# CPLD_Programming.net
KiCad netlist of a schematic drawn in Altium Designer
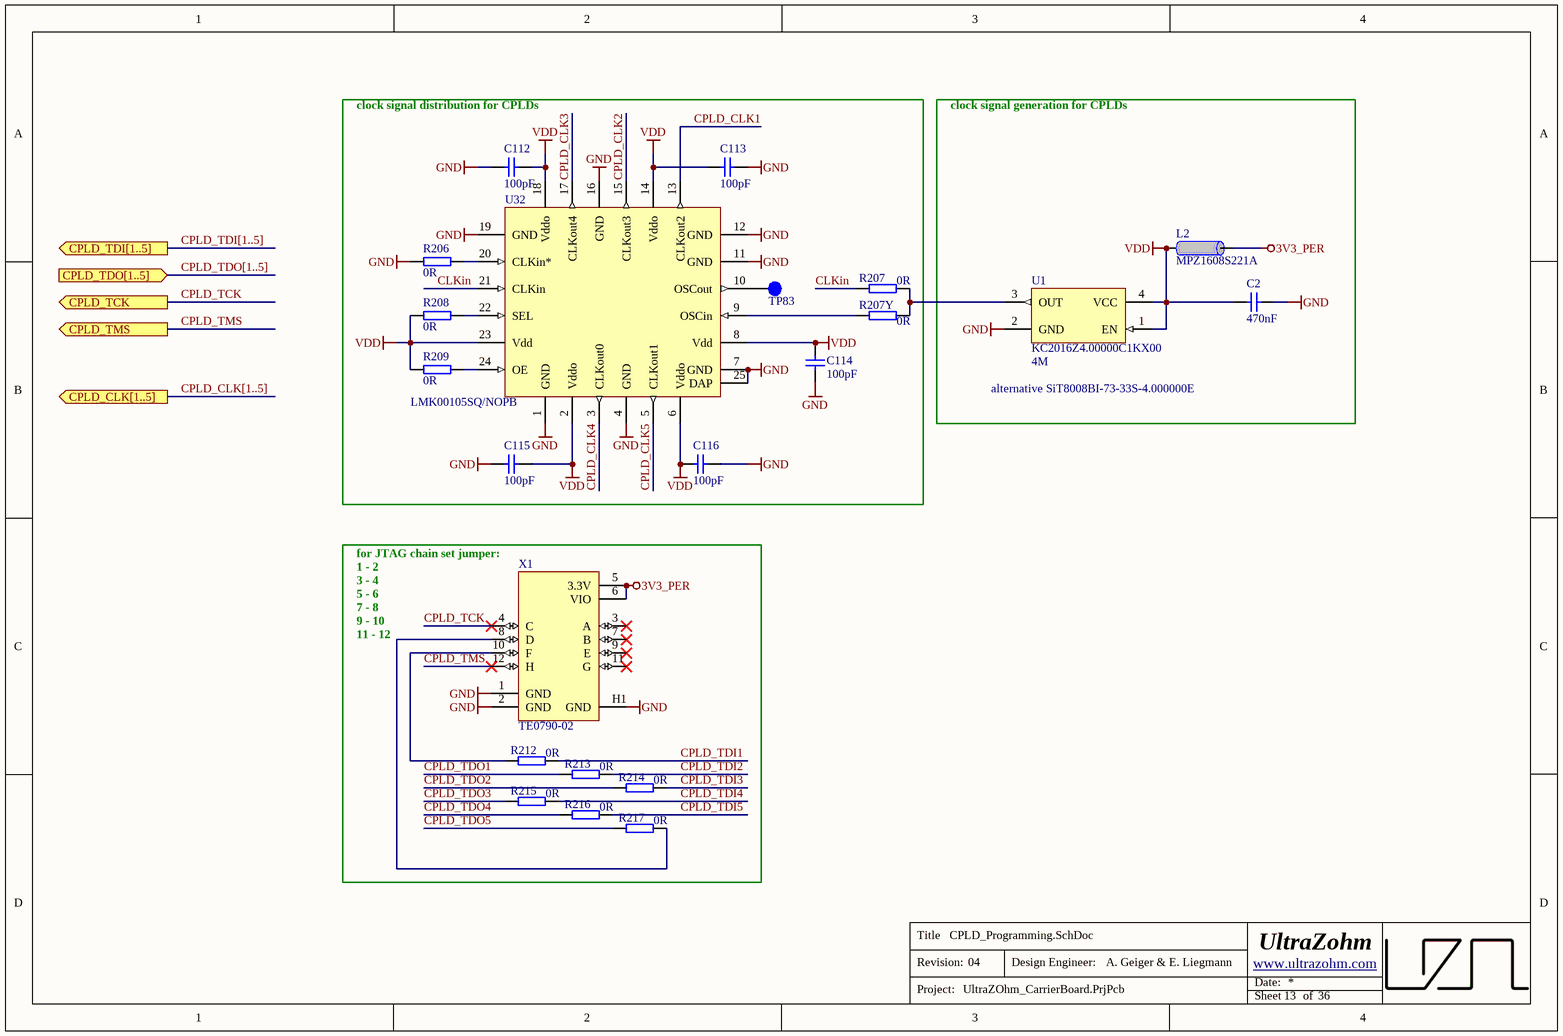
[diagram p0: CPLD_Programming.SchDoc]

(export (version "E")
  (design (tool "Eeschema 10.0.6"))
  (components
    (comp (ref "C2")
      (value "470nF")
      (footprint "CAPC1608X90N_V")
      (description "KON 470nF 50V X7R SMD  BF 1608 (0603)")
      (fields (field (name "VOLTAGE") "50V"))
      (libsource (lib "TE") (part "CAP-NP"))
    )
    (comp (ref "C112")
      (value "100pF")
      (footprint "CAPC1608X90N_V")
      (description "KON 100pF 50V NP0 ±5% SMD BF 1608 (0603)")
      (fields (field (name "TOLERANCE") "±5%") (field (name "VOLTAGE") "50V"))
      (libsource (lib "TE") (part "CAP-NP"))
    )
    (comp (ref "C113")
      (value "100pF")
      (footprint "CAPC1608X90N_V")
      (description "KON 100pF 50V NP0 ±5% SMD BF 1608 (0603)")
      (fields (field (name "TOLERANCE") "±5%") (field (name "VOLTAGE") "50V"))
      (libsource (lib "TE") (part "CAP-NP"))
    )
    (comp (ref "C114")
      (value "100pF")
      (footprint "CAPC1608X90N_V")
      (description "KON 100pF 50V NP0 ±5% SMD BF 1608 (0603)")
      (fields (field (name "TOLERANCE") "±5%") (field (name "VOLTAGE") "50V"))
      (libsource (lib "TE") (part "CAP-NP"))
    )
    (comp (ref "C115")
      (value "100pF")
      (footprint "CAPC1608X90N_V")
      (description "KON 100pF 50V NP0 ±5% SMD BF 1608 (0603)")
      (fields (field (name "TOLERANCE") "±5%") (field (name "VOLTAGE") "50V"))
      (libsource (lib "TE") (part "CAP-NP"))
    )
    (comp (ref "C116")
      (value "100pF")
      (footprint "CAPC1608X90N_V")
      (description "KON 100pF 50V NP0 ±5% SMD BF 1608 (0603)")
      (fields (field (name "TOLERANCE") "±5%") (field (name "VOLTAGE") "50V"))
      (libsource (lib "TE") (part "CAP-NP"))
    )
    (comp (ref "L2")
      (value "MPZ1608S221A")
      (footprint "INDC1608X95N_V")
      (description "Ferritdurchführung MPZ1608S221A")
      (libsource (lib "TE") (part "Ferritperle"))
    )
    (comp (ref "R206")
      (value "0R")
      (footprint "R_0603_TE")
      (description "Generic resistor")
      (fields
        (field (name "TOLERANCE") "1 %")
        (field (name "MANUFACTURER PART NUMBER") "UZgen_R_0603_0R")
        (field (name "CREATED FROM") "UZgenTool")
      )
      (libsource (lib "user") (part "RES"))
    )
    (comp (ref "R207")
      (value "0R")
      (footprint "R_0603_TE")
      (description "Generic resistor")
      (fields
        (field (name "TOLERANCE") "1 %")
        (field (name "MANUFACTURER PART NUMBER") "UZgen_R_0603_0R")
        (field (name "CREATED FROM") "UZgenTool")
      )
      (libsource (lib "user") (part "RES"))
    )
    (comp (ref "R207Y")
      (value "0R")
      (footprint "R_0603_TE")
      (description "Generic resistor")
      (fields
        (field (name "TOLERANCE") "1 %")
        (field (name "MANUFACTURER PART NUMBER") "UZgen_R_0603_0R")
        (field (name "CREATED FROM") "UZgenTool")
      )
      (libsource (lib "user") (part "RES"))
    )
    (comp (ref "R208")
      (value "0R")
      (footprint "R_0603_TE")
      (description "Generic resistor")
      (fields
        (field (name "TOLERANCE") "1 %")
        (field (name "MANUFACTURER PART NUMBER") "UZgen_R_0603_0R")
        (field (name "CREATED FROM") "UZgenTool")
      )
      (libsource (lib "user") (part "RES"))
    )
    (comp (ref "R209")
      (value "0R")
      (footprint "R_0603_TE")
      (description "Generic resistor")
      (fields
        (field (name "TOLERANCE") "1 %")
        (field (name "MANUFACTURER PART NUMBER") "UZgen_R_0603_0R")
        (field (name "CREATED FROM") "UZgenTool")
      )
      (libsource (lib "user") (part "RES"))
    )
    (comp (ref "R212")
      (value "0R")
      (footprint "R_0603_TE")
      (description "Generic resistor")
      (fields
        (field (name "TOLERANCE") "1 %")
        (field (name "MANUFACTURER PART NUMBER") "UZgen_R_0603_0R")
        (field (name "CREATED FROM") "UZgenTool")
      )
      (libsource (lib "user") (part "RES"))
    )
    (comp (ref "R213")
      (value "0R")
      (footprint "R_0603_TE")
      (description "Generic resistor")
      (fields
        (field (name "TOLERANCE") "1 %")
        (field (name "MANUFACTURER PART NUMBER") "UZgen_R_0603_0R")
        (field (name "CREATED FROM") "UZgenTool")
      )
      (libsource (lib "user") (part "RES"))
    )
    (comp (ref "R214")
      (value "0R")
      (footprint "R_0603_TE")
      (description "Generic resistor")
      (fields
        (field (name "TOLERANCE") "1 %")
        (field (name "MANUFACTURER PART NUMBER") "UZgen_R_0603_0R")
        (field (name "CREATED FROM") "UZgenTool")
      )
      (libsource (lib "user") (part "RES"))
    )
    (comp (ref "R215")
      (value "0R")
      (footprint "R_0603_TE")
      (description "Generic resistor")
      (fields
        (field (name "TOLERANCE") "1 %")
        (field (name "MANUFACTURER PART NUMBER") "UZgen_R_0603_0R")
        (field (name "CREATED FROM") "UZgenTool")
      )
      (libsource (lib "user") (part "RES"))
    )
    (comp (ref "R216")
      (value "0R")
      (footprint "R_0603_TE")
      (description "Generic resistor")
      (fields
        (field (name "TOLERANCE") "1 %")
        (field (name "MANUFACTURER PART NUMBER") "UZgen_R_0603_0R")
        (field (name "CREATED FROM") "UZgenTool")
      )
      (libsource (lib "user") (part "RES"))
    )
    (comp (ref "R217")
      (value "0R")
      (footprint "R_0603_TE")
      (description "Generic resistor")
      (fields
        (field (name "TOLERANCE") "1 %")
        (field (name "MANUFACTURER PART NUMBER") "UZgen_R_0603_0R")
        (field (name "CREATED FROM") "UZgenTool")
      )
      (libsource (lib "user") (part "RES"))
    )
    (comp (ref "TP83") (value "Testpoint 1mm") (footprint "TP_1mm") (libsource (lib "TE") (part "TP")))
    (comp (ref "U1")
      (value "KC2016Z4.00000C1KX00")
      (footprint "2016")
      (description "KC2016Z4.00000C1KX00 Oszillator 4.000000MHz")
      (fields
        (field (name "ALTIUM_VALUE") "4M")
        (field (name "VOLTAGE") "1.8-3.3V")
        (field (name "TOLERANCE") "20ppm")
      )
      (libsource (lib "TE") (part "KC3225K"))
    )
    (comp (ref "U32")
      (value "LMK00105SQ/NOPB")
      (footprint "QFN50P400X400X80-25N")
      (libsource (lib "TE") (part "LMK00105"))
    )
    (comp (ref "X1")
      (value "TE0790-02")
      (footprint "TE0790-Base")
      (description "Adapter USG, JTAG, XMOD, FTDI 2CH")
      (fields (field (name "MANUFACTURER") "Trenz Electronic GmbH") (field (name "CREATED FROM") "MGremer"))
      (libsource (lib "user") (part "TE0790-JB"))
    )
  )
  (nets
    (net (code "1") (name "/CLKin") (class "Default")
      (node (ref "R207") (pin "1") (pinfunction "1_1") (pintype "passive"))
      (node (ref "U32") (pin "21") (pinfunction "CLKin_21") (pintype "input"))
    )
    (net (code "2") (name "/CPLD_CLK1") (class "Default")
      (node (ref "U32") (pin "13") (pinfunction "CLKout2_13") (pintype "output"))
    )
    (net (code "3") (name "/CPLD_CLK2") (class "Default")
      (node (ref "U32") (pin "15") (pinfunction "CLKout3_15") (pintype "output"))
    )
    (net (code "4") (name "/CPLD_CLK3") (class "Default")
      (node (ref "U32") (pin "17") (pinfunction "CLKout4_17") (pintype "output"))
    )
    (net (code "5") (name "/CPLD_CLK4") (class "Default")
      (node (ref "U32") (pin "3") (pinfunction "CLKout0_3") (pintype "output"))
    )
    (net (code "6") (name "/CPLD_CLK5") (class "Default")
      (node (ref "U32") (pin "5") (pinfunction "CLKout1_5") (pintype "output"))
    )
    (net (code "8") (name "/CPLD_TCK") (class "Default")
      (node (ref "X1") (pin "4") (pinfunction "C_4") (pintype "bidirectional+no_connect"))
    )
    (net (code "9") (name "/CPLD_TDI1") (class "Default")
      (node (ref "R212") (pin "2") (pinfunction "2_2") (pintype "passive"))
    )
    (net (code "10") (name "/CPLD_TDI2") (class "Default")
      (node (ref "R213") (pin "2") (pinfunction "2_2") (pintype "passive"))
    )
    (net (code "11") (name "/CPLD_TDI3") (class "Default")
      (node (ref "R214") (pin "2") (pinfunction "2_2") (pintype "passive"))
    )
    (net (code "12") (name "/CPLD_TDI4") (class "Default")
      (node (ref "R215") (pin "2") (pinfunction "2_2") (pintype "passive"))
    )
    (net (code "13") (name "/CPLD_TDI5") (class "Default")
      (node (ref "R216") (pin "2") (pinfunction "2_2") (pintype "passive"))
    )
    (net (code "15") (name "/CPLD_TDO1") (class "Default")
      (node (ref "R213") (pin "1") (pinfunction "1_1") (pintype "passive"))
    )
    (net (code "16") (name "/CPLD_TDO2") (class "Default")
      (node (ref "R214") (pin "1") (pinfunction "1_1") (pintype "passive"))
    )
    (net (code "17") (name "/CPLD_TDO3") (class "Default")
      (node (ref "R215") (pin "1") (pinfunction "1_1") (pintype "passive"))
    )
    (net (code "18") (name "/CPLD_TDO4") (class "Default")
      (node (ref "R216") (pin "1") (pinfunction "1_1") (pintype "passive"))
    )
    (net (code "19") (name "/CPLD_TDO5") (class "Default")
      (node (ref "R217") (pin "1") (pinfunction "1_1") (pintype "passive"))
    )
    (net (code "21") (name "/CPLD_TMS") (class "Default")
      (node (ref "X1") (pin "12") (pinfunction "H_12") (pintype "bidirectional+no_connect"))
    )
    (net (code "22") (name "3V3_PER") (class "Default")
      (node (ref "L2") (pin "2") (pinfunction "2_2") (pintype "passive"))
      (node (ref "X1") (pin "5") (pinfunction "3.3V_5") (pintype "power_in"))
      (node (ref "X1") (pin "6") (pinfunction "VIO_6") (pintype "power_in"))
    )
    (net (code "23") (name "GND") (class "Default")
      (node (ref "C112") (pin "2") (pinfunction "2_2") (pintype "passive"))
      (node (ref "C113") (pin "1") (pinfunction "1_1") (pintype "passive"))
      (node (ref "C114") (pin "2") (pinfunction "2_2") (pintype "passive"))
      (node (ref "C115") (pin "2") (pinfunction "2_2") (pintype "passive"))
      (node (ref "C116") (pin "1") (pinfunction "1_1") (pintype "passive"))
      (node (ref "C2") (pin "1") (pinfunction "1_1") (pintype "passive"))
      (node (ref "R206") (pin "2") (pinfunction "2_2") (pintype "passive"))
      (node (ref "U1") (pin "2") (pinfunction "GND_2") (pintype "power_in"))
      (node (ref "U32") (pin "1") (pinfunction "GND_1") (pintype "passive"))
      (node (ref "U32") (pin "11") (pinfunction "GND_11") (pintype "passive"))
      (node (ref "U32") (pin "12") (pinfunction "GND_12") (pintype "passive"))
      (node (ref "U32") (pin "16") (pinfunction "GND_16") (pintype "passive"))
      (node (ref "U32") (pin "19") (pinfunction "GND_19") (pintype "passive"))
      (node (ref "U32") (pin "25") (pinfunction "DAP_25") (pintype "passive"))
      (node (ref "U32") (pin "4") (pinfunction "GND_4") (pintype "passive"))
      (node (ref "U32") (pin "7") (pinfunction "GND_7") (pintype "passive"))
      (node (ref "X1") (pin "1") (pinfunction "GND_1") (pintype "power_in"))
      (node (ref "X1") (pin "2") (pinfunction "GND_2") (pintype "power_in"))
      (node (ref "X1") (pin "H1") (pinfunction "GND_H1") (pintype "power_in"))
    )
    (net (code "24") (name "Net-(U1-OUT)") (class "Default")
      (node (ref "R207") (pin "2") (pinfunction "2_2") (pintype "passive"))
      (node (ref "R207Y") (pin "2") (pinfunction "2_2") (pintype "passive"))
      (node (ref "U1") (pin "3") (pinfunction "OUT_3") (pintype "output"))
    )
    (net (code "25") (name "Net-(U32-CLKin*)") (class "Default")
      (node (ref "R206") (pin "1") (pinfunction "1_1") (pintype "passive"))
      (node (ref "U32") (pin "20") (pinfunction "CLKin*_20") (pintype "input"))
    )
    (net (code "26") (name "Net-(U32-OE)") (class "Default")
      (node (ref "R209") (pin "1") (pinfunction "1_1") (pintype "passive"))
      (node (ref "U32") (pin "24") (pinfunction "OE_24") (pintype "input"))
    )
    (net (code "27") (name "Net-(U32-OSCin)") (class "Default")
      (node (ref "R207Y") (pin "1") (pinfunction "1_1") (pintype "passive"))
      (node (ref "U32") (pin "9") (pinfunction "OSCin_9") (pintype "input"))
    )
    (net (code "28") (name "Net-(U32-OSCout)") (class "Default")
      (node (ref "TP83") (pin "1") (pintype "passive"))
      (node (ref "U32") (pin "10") (pinfunction "OSCout_10") (pintype "output"))
    )
    (net (code "29") (name "Net-(U32-SEL)") (class "Default")
      (node (ref "R208") (pin "2") (pinfunction "2_2") (pintype "passive"))
      (node (ref "U32") (pin "22") (pinfunction "SEL_22") (pintype "input"))
    )
    (net (code "30") (name "Net-(X1-D)") (class "Default")
      (node (ref "R217") (pin "2") (pinfunction "2_2") (pintype "passive"))
      (node (ref "X1") (pin "8") (pinfunction "D_8") (pintype "bidirectional"))
    )
    (net (code "31") (name "Net-(X1-F)") (class "Default")
      (node (ref "R212") (pin "1") (pinfunction "1_1") (pintype "passive"))
      (node (ref "X1") (pin "10") (pinfunction "F_10") (pintype "bidirectional"))
    )
    (net (code "32") (name "VDD") (class "Default")
      (node (ref "C112") (pin "1") (pinfunction "1_1") (pintype "passive"))
      (node (ref "C113") (pin "2") (pinfunction "2_2") (pintype "passive"))
      (node (ref "C114") (pin "1") (pinfunction "1_1") (pintype "passive"))
      (node (ref "C115") (pin "1") (pinfunction "1_1") (pintype "passive"))
      (node (ref "C116") (pin "2") (pinfunction "2_2") (pintype "passive"))
      (node (ref "C2") (pin "2") (pinfunction "2_2") (pintype "passive"))
      (node (ref "L2") (pin "1") (pinfunction "1_1") (pintype "passive"))
      (node (ref "R208") (pin "1") (pinfunction "1_1") (pintype "passive"))
      (node (ref "R209") (pin "2") (pinfunction "2_2") (pintype "passive"))
      (node (ref "U1") (pin "1") (pinfunction "EN_1") (pintype "input"))
      (node (ref "U1") (pin "4") (pinfunction "VCC_4") (pintype "power_in"))
      (node (ref "U32") (pin "14") (pinfunction "Vddo_14") (pintype "power_in"))
      (node (ref "U32") (pin "18") (pinfunction "Vddo_18") (pintype "power_in"))
      (node (ref "U32") (pin "2") (pinfunction "Vddo_2") (pintype "passive"))
      (node (ref "U32") (pin "23") (pinfunction "Vdd_23") (pintype "power_in"))
      (node (ref "U32") (pin "6") (pinfunction "Vddo_6") (pintype "power_in"))
      (node (ref "U32") (pin "8") (pinfunction "Vdd_8") (pintype "power_in"))
    )
    (net (code "33") (name "unconnected-(X1-A-Pad3)") (class "Default")
      (node (ref "X1") (pin "3") (pinfunction "A_3") (pintype "bidirectional+no_connect"))
    )
    (net (code "34") (name "unconnected-(X1-B-Pad7)") (class "Default")
      (node (ref "X1") (pin "7") (pinfunction "B_7") (pintype "bidirectional+no_connect"))
    )
    (net (code "35") (name "unconnected-(X1-E-Pad9)") (class "Default")
      (node (ref "X1") (pin "9") (pinfunction "E_9") (pintype "bidirectional+no_connect"))
    )
    (net (code "36") (name "unconnected-(X1-G-Pad11)") (class "Default")
      (node (ref "X1") (pin "11") (pinfunction "G_11") (pintype "bidirectional+no_connect"))
    )
  )
)
